# Shield_Amir_Shalev_V_0_0.net
KiCad netlist of a schematic drawn in EasyEDA
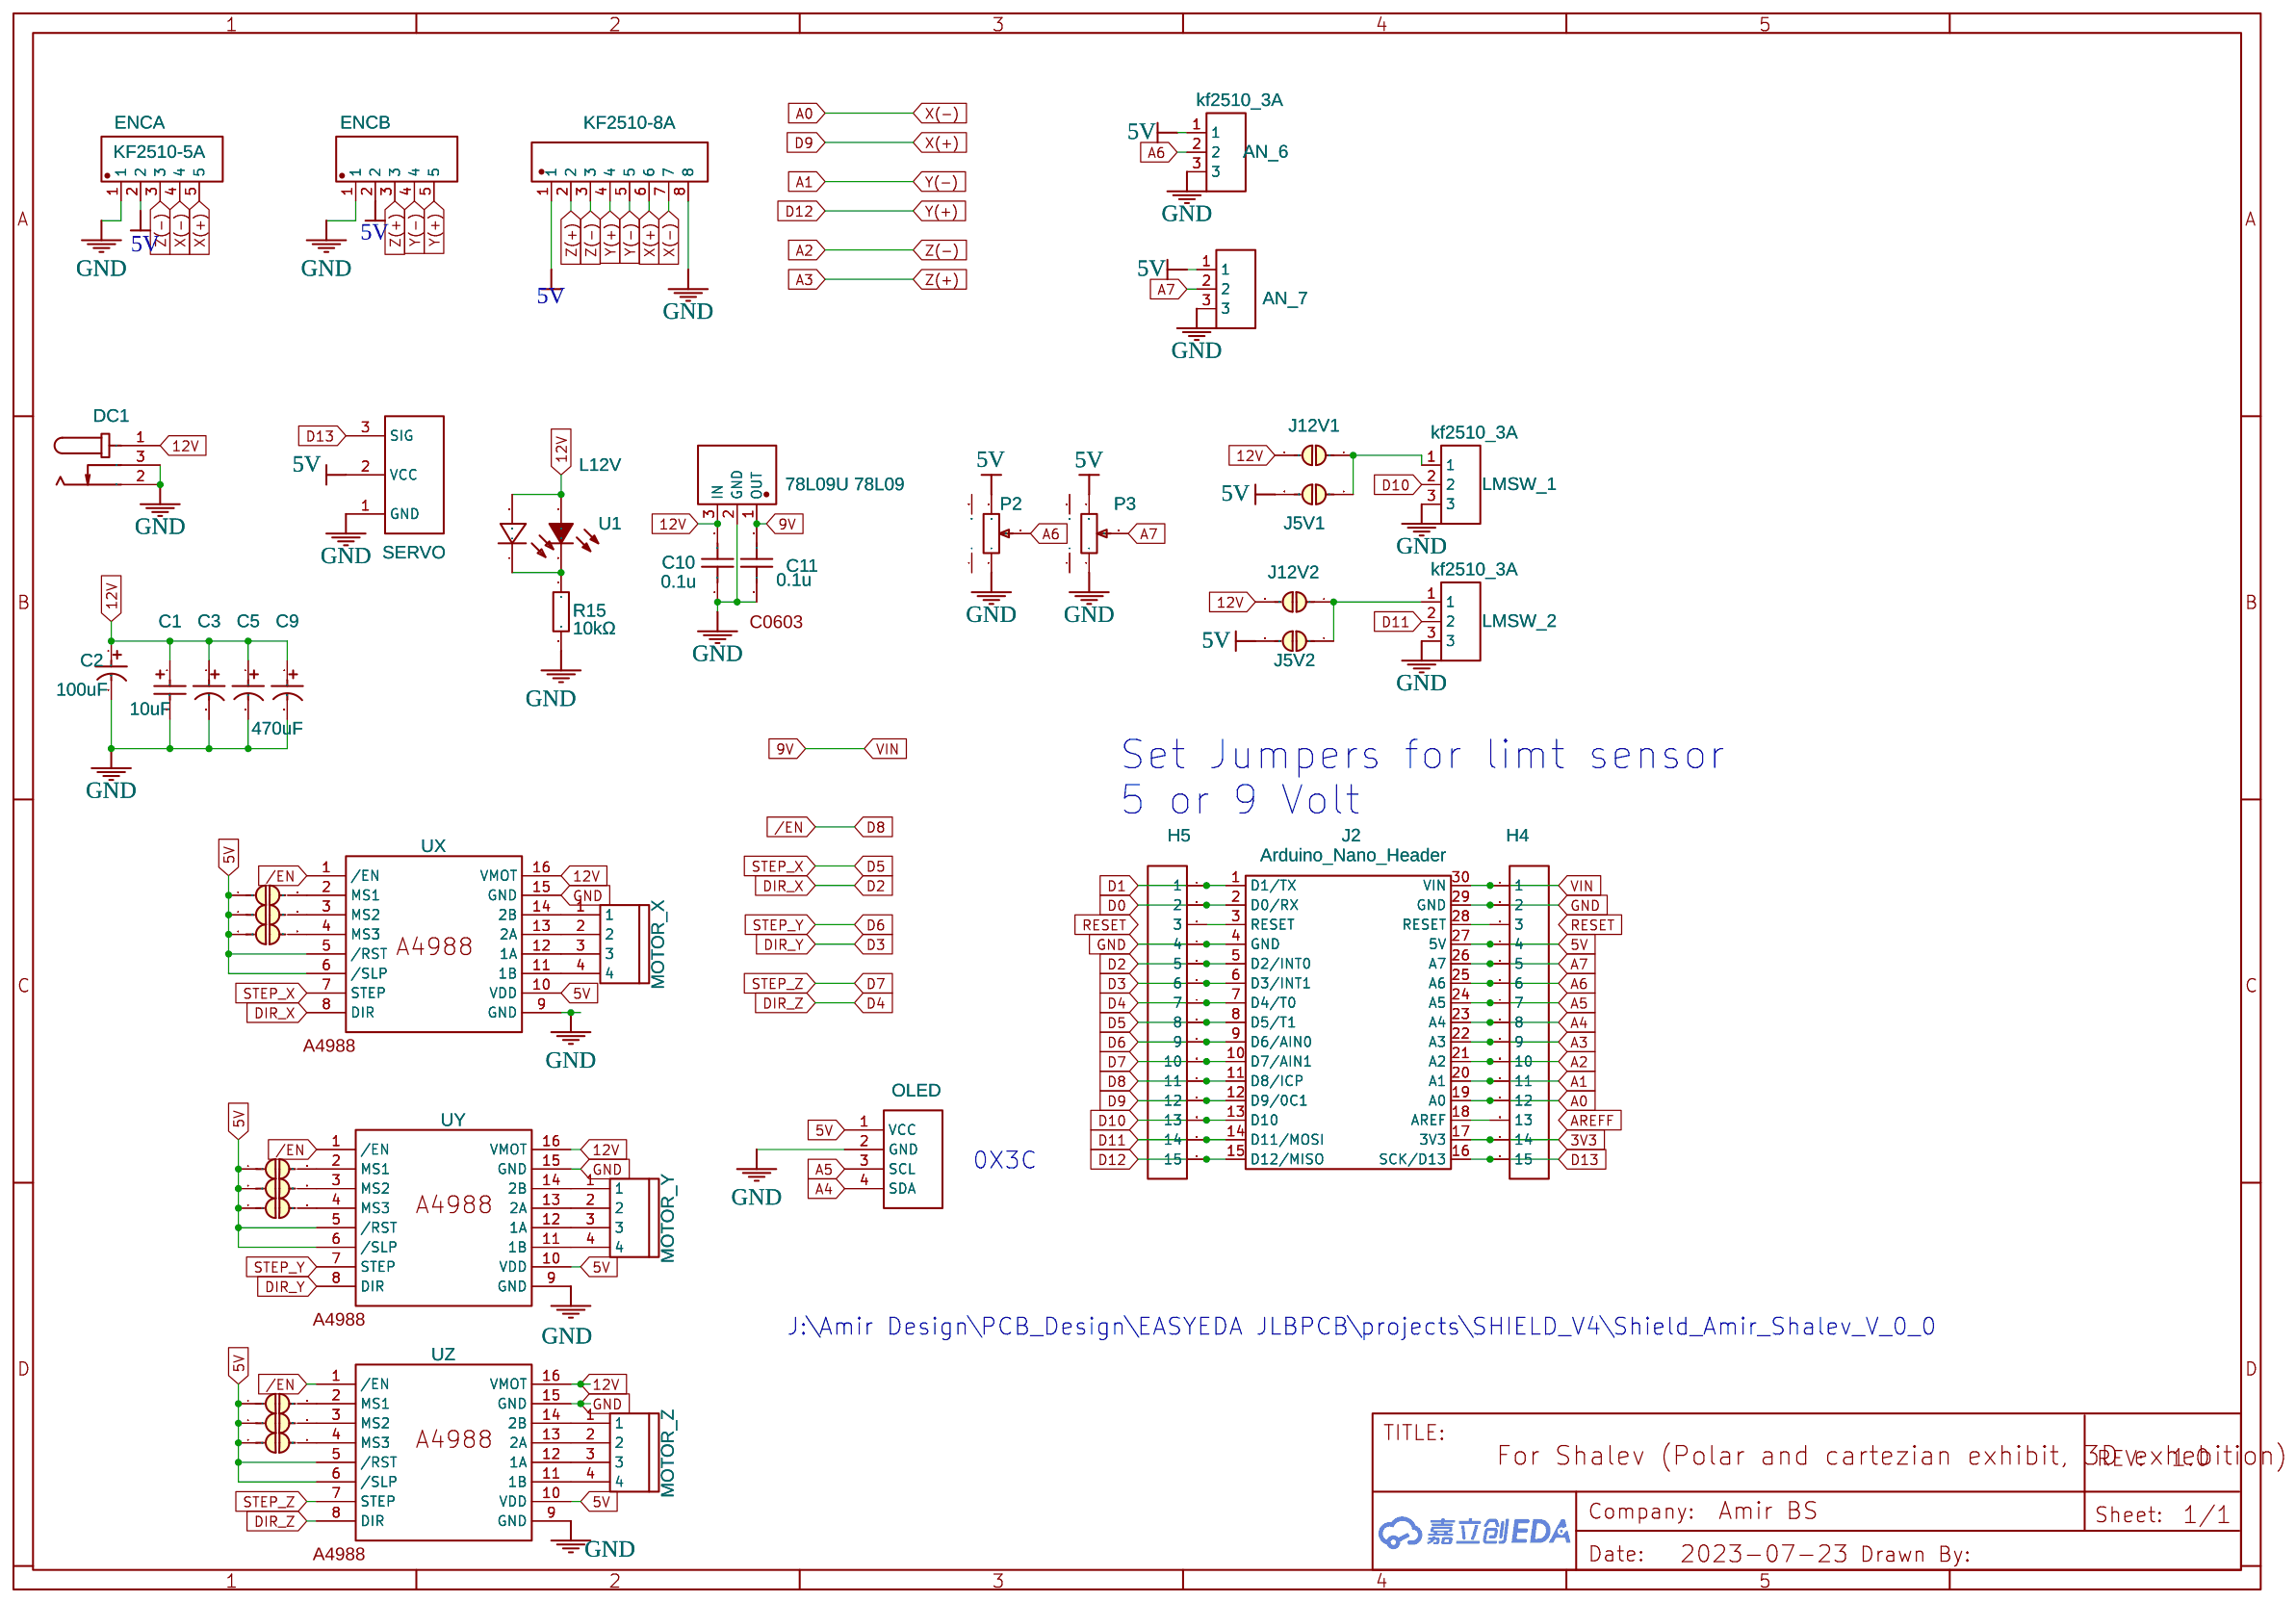
[diagram p0: schematic sheet]

(export (version "E")
  (design (tool "Eeschema 10.0.6"))
  (components
    (comp (ref "AN_6")
      (value "kf2510_3A")
      (fields (field (name "Manufacturer Part") "2510-3A") (field (name "Manufacturer") "BOOMELE(博穆精密)"))
      (libsource (lib "") (part "kf2510_3A_1"))
    )
    (comp (ref "AN_7")
      (value "kf2510_3A")
      (fields (field (name "Manufacturer Part") "2510-3A") (field (name "Manufacturer") "BOOMELE(博穆精密)"))
      (libsource (lib "") (part "kf2510_3A_1"))
    )
    (comp (ref "C1")
      (value "10uF")
      (fields (field (name "Manufacturer Part") "TAJA106K016RNJ") (field (name "Manufacturer") "Kyocera AVX"))
      (libsource (lib "") (part "TAJA106K016RNJ"))
    )
    (comp (ref "C2")
      (value "100uF")
      (fields
        (field (name "Manufacturer Part") "KM107M035E11RR0VH2FP0")
        (field (name "Manufacturer") "CX(承兴)")
      )
      (libsource (lib "") (part "100uF 35V 6.3*11"))
    )
    (comp (ref "C3")
      (value "470uF")
      (fields
        (field (name "Manufacturer Part") "GR477M025F12RR0VH4FP0")
        (field (name "Manufacturer") "CX(承兴)")
      )
      (libsource (lib "") (part "470uF 25V 8*12Black high frequency"))
    )
    (comp (ref "C5")
      (value "470uF")
      (fields
        (field (name "Manufacturer Part") "GR477M025F12RR0VH4FP0")
        (field (name "Manufacturer") "CX(承兴)")
      )
      (libsource (lib "") (part "470uF 25V 8*12Black high frequency"))
    )
    (comp (ref "C9")
      (value "470uF")
      (fields
        (field (name "Manufacturer Part") "GR477M025F12RR0VH4FP0")
        (field (name "Manufacturer") "CX(承兴)")
      )
      (libsource (lib "") (part "470uF 25V 8*12Black high frequency"))
    )
    (comp (ref "C10") (value "0.1u") (libsource (lib "") (part "C_0603_US")))
    (comp (ref "C11") (value "0.1u") (libsource (lib "") (part "C_0603_US_1")))
    (comp (ref "CN2")
      (value "KF2510-8A")
      (fields (field (name "Manufacturer Part") "2510-8A") (field (name "Manufacturer") "BOOMELE(博穆精密)"))
      (libsource (lib "") (part "KF2510-8A"))
    )
    (comp (ref "DC1")
      (value "DC")
      (fields
        (field (name "BOM_Manufacturer Part") "DC005-2.0MM")
        (field (name "BOM_Supplier Part") "C111567")
      )
      (libsource (lib "") (part "DC005-2.0MM"))
    )
    (comp (ref "ENCA")
      (value "KF2510-5A")
      (fields (field (name "Manufacturer Part") "2510-5A") (field (name "Manufacturer") "BOOMELE(博穆精密)"))
      (libsource (lib "") (part "KF2510-5A_1"))
    )
    (comp (ref "ENCB")
      (value "KF2510-5A")
      (fields (field (name "Manufacturer Part") "2510-5A") (field (name "Manufacturer") "BOOMELE(博穆精密)"))
      (libsource (lib "") (part "KF2510-5A"))
    )
    (comp (ref "H4")
      (value "HDR-F-2.54_1x15")
      (fields (field (name "BOM_Supplier Part") "C124408"))
      (libsource (lib "") (part "HDR-F-2.54_1x15"))
    )
    (comp (ref "H5")
      (value "HDR-F-2.54_1x15")
      (fields (field (name "BOM_Supplier Part") "C124408"))
      (libsource (lib "") (part "HDR-F-2.54_1x15_1"))
    )
    (comp (ref "J2") (value "Arduino_Nano_Header") (libsource (lib "") (part "Arduino_Nano_Header")))
    (comp (ref "J5V1") (value "JUMPER-SMT_2") (libsource (lib "") (part "JUMPER-SMT_2_3")))
    (comp (ref "J5V2") (value "JUMPER-SMT_2") (libsource (lib "") (part "JUMPER-SMT_2_3")))
    (comp (ref "J12V1") (value "JUMPER-SMT_2") (libsource (lib "") (part "JUMPER-SMT_2_4")))
    (comp (ref "J12V2") (value "JUMPER-SMT_2") (libsource (lib "") (part "JUMPER-SMT_2_4")))
    (comp (ref "JX1") (value "JUMPER-SMT_2") (libsource (lib "") (part "JUMPER-SMT_2")))
    (comp (ref "JX2") (value "JUMPER-SMT_2") (libsource (lib "") (part "JUMPER-SMT_2")))
    (comp (ref "JX3") (value "JUMPER-SMT_2") (libsource (lib "") (part "JUMPER-SMT_2")))
    (comp (ref "JY1") (value "JUMPER-SMT_2") (libsource (lib "") (part "JUMPER-SMT_2_1")))
    (comp (ref "JY2") (value "JUMPER-SMT_2") (libsource (lib "") (part "JUMPER-SMT_2_1")))
    (comp (ref "JY3") (value "JUMPER-SMT_2") (libsource (lib "") (part "JUMPER-SMT_2_1")))
    (comp (ref "JZ1") (value "JUMPER-SMT_2") (libsource (lib "") (part "JUMPER-SMT_2_2")))
    (comp (ref "JZ2") (value "JUMPER-SMT_2") (libsource (lib "") (part "JUMPER-SMT_2_2")))
    (comp (ref "JZ3") (value "JUMPER-SMT_2") (libsource (lib "") (part "JUMPER-SMT_2_2")))
    (comp (ref "L12V")
      (value "LED")
      (fields
        (field (name "BOM_Manufacturer Part") "19-217/BHC-ZL1M2RY/3T")
        (field (name "BOM_Supplier Part") "C72041")
      )
      (libsource (lib "") (part "19-217/BHC-ZL1M2RY/3T"))
    )
    (comp (ref "LMSW_1")
      (value "kf2510_3A")
      (fields (field (name "Manufacturer Part") "2510-3A") (field (name "Manufacturer") "BOOMELE(博穆精密)"))
      (libsource (lib "") (part "kf2510_3A"))
    )
    (comp (ref "LMSW_2")
      (value "kf2510_3A")
      (fields (field (name "Manufacturer Part") "2510-3A") (field (name "Manufacturer") "BOOMELE(博穆精密)"))
      (libsource (lib "") (part "kf2510_3A"))
    )
    (comp (ref "MOTOR_X")
      (value "XH2.54-4AW")
      (fields (field (name "Manufacturer Part") "XH-4AW") (field (name "Manufacturer") "BOOMELE(博穆精密)"))
      (libsource (lib "") (part "XH2.54-4AW"))
    )
    (comp (ref "MOTOR_Y")
      (value "XH2.54-4AW")
      (fields (field (name "Manufacturer Part") "XH-4AW") (field (name "Manufacturer") "BOOMELE(博穆精密)"))
      (libsource (lib "") (part "XH2.54-4AW_2"))
    )
    (comp (ref "MOTOR_Z")
      (value "XH2.54-4AW")
      (fields (field (name "Manufacturer Part") "XH-4AW") (field (name "Manufacturer") "BOOMELE(博穆精密)"))
      (libsource (lib "") (part "XH2.54-4AW_1"))
    )
    (comp (ref "OLED")
      (value "1.3 inch OLED SSH1106 I2C 128x64 copy")
      (libsource (lib "") (part "1.3 inch OLED SSH1106 I2C 128x64 copy"))
    )
    (comp (ref "P2")
      (value "长柄旋转电位器")
      (fields (field (name "BOM_Supplier Part") "C2874842"))
      (libsource (lib "") (part "长柄旋转电位器"))
    )
    (comp (ref "P3")
      (value "长柄旋转电位器")
      (fields (field (name "BOM_Supplier Part") "C2874842"))
      (libsource (lib "") (part "长柄旋转电位器"))
    )
    (comp (ref "R15")
      (value "10kΩ")
      (fields
        (field (name "BOM_Manufacturer Part") "0603WAF1002T5E")
        (field (name "BOM_Supplier Part") "C25804")
      )
      (libsource (lib "") (part "0603WAF1002T5E"))
    )
    (comp (ref "SERVO")
      (value "Servo+3d")
      (fields (field (name "BOM_Manufacturer Part") "New SchematicLib"))
      (libsource (lib "") (part "Servo+3d"))
    )
    (comp (ref "U1")
      (value "LED-DIP-3MM_RED")
      (fields (field (name "Manufacturer Part") "LED-DIP-3MM_Red"))
      (libsource (lib "") (part "LED-DIP-3MM_RED"))
    )
    (comp (ref "U5")
      (value "78L09U 78L09")
      (fields (field (name "Manufacturer") "CBI(创基)"))
      (libsource (lib "") (part "78L09U 78L09"))
    )
    (comp (ref "UX") (value "A4988") (libsource (lib "") (part "A4988_2")))
    (comp (ref "UY") (value "A4988") (libsource (lib "") (part "A4988")))
    (comp (ref "UZ") (value "A4988") (libsource (lib "") (part "A4988_1")))
  )
  (nets
    (net (code "1") (name "3V3") (class "Default")
      (node (ref "H4") (pin "14") (pinfunction "14_14") (pintype "unspecified"))
      (node (ref "J2") (pin "17") (pinfunction "3V3_17") (pintype "unspecified"))
    )
    (net (code "2") (name "5V") (class "Default")
      (node (ref "AN_6") (pin "1") (pinfunction "1_1") (pintype "unspecified"))
      (node (ref "AN_7") (pin "1") (pinfunction "1_1") (pintype "unspecified"))
      (node (ref "CN2") (pin "1") (pinfunction "1_1") (pintype "unspecified"))
      (node (ref "ENCA") (pin "2") (pinfunction "2_2") (pintype "unspecified"))
      (node (ref "ENCB") (pin "2") (pinfunction "2_2") (pintype "unspecified"))
      (node (ref "H4") (pin "4") (pinfunction "4_4") (pintype "unspecified"))
      (node (ref "J2") (pin "27") (pinfunction "5V_27") (pintype "unspecified"))
      (node (ref "J5V1") (pin "2") (pinfunction "2_2") (pintype "bidirectional"))
      (node (ref "J5V2") (pin "2") (pinfunction "2_2") (pintype "bidirectional"))
      (node (ref "JX1") (pin "1") (pinfunction "1_1") (pintype "bidirectional"))
      (node (ref "JX2") (pin "1") (pinfunction "1_1") (pintype "bidirectional"))
      (node (ref "JX3") (pin "1") (pinfunction "1_1") (pintype "bidirectional"))
      (node (ref "JY1") (pin "1") (pinfunction "1_1") (pintype "bidirectional"))
      (node (ref "JY2") (pin "1") (pinfunction "1_1") (pintype "bidirectional"))
      (node (ref "JY3") (pin "1") (pinfunction "1_1") (pintype "bidirectional"))
      (node (ref "JZ1") (pin "1") (pinfunction "1_1") (pintype "bidirectional"))
      (node (ref "JZ2") (pin "1") (pinfunction "1_1") (pintype "bidirectional"))
      (node (ref "JZ3") (pin "1") (pinfunction "1_1") (pintype "bidirectional"))
      (node (ref "OLED") (pin "1") (pinfunction "VCC_1") (pintype "passive"))
      (node (ref "P2") (pin "3") (pinfunction "3_3") (pintype "input"))
      (node (ref "P3") (pin "3") (pinfunction "3_3") (pintype "input"))
      (node (ref "SERVO") (pin "2") (pinfunction "VCC_2") (pintype "unspecified"))
      (node (ref "UX") (pin "10") (pinfunction "VDD_10") (pintype "unspecified"))
      (node (ref "UX") (pin "5") (pinfunction "/RST_5") (pintype "unspecified"))
      (node (ref "UX") (pin "6") (pinfunction "/SLP_6") (pintype "unspecified"))
      (node (ref "UY") (pin "10") (pinfunction "VDD_10") (pintype "unspecified"))
      (node (ref "UY") (pin "5") (pinfunction "/RST_5") (pintype "unspecified"))
      (node (ref "UY") (pin "6") (pinfunction "/SLP_6") (pintype "unspecified"))
      (node (ref "UZ") (pin "10") (pinfunction "VDD_10") (pintype "unspecified"))
      (node (ref "UZ") (pin "5") (pinfunction "/RST_5") (pintype "unspecified"))
      (node (ref "UZ") (pin "6") (pinfunction "/SLP_6") (pintype "unspecified"))
    )
    (net (code "3") (name "9V") (class "Default")
      (node (ref "C11") (pin "2") (pinfunction "2_2") (pintype "unspecified"))
      (node (ref "H4") (pin "1") (pinfunction "1_1") (pintype "unspecified"))
      (node (ref "J2") (pin "30") (pinfunction "VIN_30") (pintype "unspecified"))
      (node (ref "U5") (pin "1") (pinfunction "OUT_1") (pintype "unspecified"))
    )
    (net (code "4") (name "12V") (class "Default")
      (node (ref "C1") (pin "1") (pinfunction "1_1") (pintype "input"))
      (node (ref "C10") (pin "2") (pinfunction "2_2") (pintype "unspecified"))
      (node (ref "C2") (pin "1") (pinfunction "1_1") (pintype "input"))
      (node (ref "C3") (pin "1") (pinfunction "1_1") (pintype "input"))
      (node (ref "C5") (pin "1") (pinfunction "1_1") (pintype "input"))
      (node (ref "C9") (pin "1") (pinfunction "1_1") (pintype "input"))
      (node (ref "DC1") (pin "1") (pinfunction "1_1") (pintype "unspecified"))
      (node (ref "J12V1") (pin "2") (pinfunction "2_2") (pintype "bidirectional"))
      (node (ref "J12V2") (pin "2") (pinfunction "2_2") (pintype "bidirectional"))
      (node (ref "L12V") (pin "1") (pinfunction "A_1") (pintype "input"))
      (node (ref "U1") (pin "2") (pinfunction "2_2") (pintype "unspecified"))
      (node (ref "U5") (pin "3") (pinfunction "IN_3") (pintype "unspecified"))
      (node (ref "UX") (pin "16") (pinfunction "VMOT_16") (pintype "unspecified"))
      (node (ref "UY") (pin "16") (pinfunction "VMOT_16") (pintype "unspecified"))
      (node (ref "UZ") (pin "16") (pinfunction "VMOT_16") (pintype "unspecified"))
    )
    (net (code "5") (name "A0") (class "Default")
      (node (ref "CN2") (pin "7") (pinfunction "7_7") (pintype "unspecified"))
      (node (ref "ENCA") (pin "4") (pinfunction "4_4") (pintype "unspecified"))
      (node (ref "H4") (pin "12") (pinfunction "12_12") (pintype "unspecified"))
      (node (ref "J2") (pin "19") (pinfunction "A0_19") (pintype "unspecified"))
    )
    (net (code "6") (name "A1") (class "Default")
      (node (ref "CN2") (pin "5") (pinfunction "5_5") (pintype "unspecified"))
      (node (ref "ENCB") (pin "4") (pinfunction "4_4") (pintype "unspecified"))
      (node (ref "H4") (pin "11") (pinfunction "11_11") (pintype "unspecified"))
      (node (ref "J2") (pin "20") (pinfunction "A1_20") (pintype "unspecified"))
    )
    (net (code "7") (name "A2") (class "Default")
      (node (ref "CN2") (pin "3") (pinfunction "3_3") (pintype "unspecified"))
      (node (ref "ENCA") (pin "3") (pinfunction "3_3") (pintype "unspecified"))
      (node (ref "H4") (pin "10") (pinfunction "10_10") (pintype "unspecified"))
      (node (ref "J2") (pin "21") (pinfunction "A2_21") (pintype "unspecified"))
    )
    (net (code "8") (name "A3") (class "Default")
      (node (ref "CN2") (pin "2") (pinfunction "2_2") (pintype "unspecified"))
      (node (ref "ENCB") (pin "3") (pinfunction "3_3") (pintype "unspecified"))
      (node (ref "H4") (pin "9") (pinfunction "9_9") (pintype "unspecified"))
      (node (ref "J2") (pin "22") (pinfunction "A3_22") (pintype "unspecified"))
    )
    (net (code "9") (name "A4") (class "Default")
      (node (ref "H4") (pin "8") (pinfunction "8_8") (pintype "unspecified"))
      (node (ref "J2") (pin "23") (pinfunction "A4_23") (pintype "unspecified"))
      (node (ref "OLED") (pin "4") (pinfunction "SDA_4") (pintype "bidirectional"))
    )
    (net (code "10") (name "A5") (class "Default")
      (node (ref "H4") (pin "7") (pinfunction "7_7") (pintype "unspecified"))
      (node (ref "J2") (pin "24") (pinfunction "A5_24") (pintype "unspecified"))
      (node (ref "OLED") (pin "3") (pinfunction "SCL_3") (pintype "bidirectional"))
    )
    (net (code "11") (name "A6") (class "Default")
      (node (ref "AN_6") (pin "2") (pinfunction "2_2") (pintype "unspecified"))
      (node (ref "H4") (pin "6") (pinfunction "6_6") (pintype "unspecified"))
      (node (ref "J2") (pin "25") (pinfunction "A6_25") (pintype "unspecified"))
      (node (ref "P2") (pin "2") (pinfunction "2_2") (pintype "input"))
    )
    (net (code "12") (name "A7") (class "Default")
      (node (ref "AN_7") (pin "2") (pinfunction "2_2") (pintype "unspecified"))
      (node (ref "H4") (pin "5") (pinfunction "5_5") (pintype "unspecified"))
      (node (ref "J2") (pin "26") (pinfunction "A7_26") (pintype "unspecified"))
      (node (ref "P3") (pin "2") (pinfunction "2_2") (pintype "input"))
    )
    (net (code "14") (name "D0") (class "Default")
      (node (ref "H5") (pin "2") (pinfunction "2_2") (pintype "unspecified"))
      (node (ref "J2") (pin "2") (pinfunction "D0/RX_2") (pintype "unspecified"))
    )
    (net (code "15") (name "D1") (class "Default")
      (node (ref "H5") (pin "1") (pinfunction "1_1") (pintype "unspecified"))
      (node (ref "J2") (pin "1") (pinfunction "D1/TX_1") (pintype "unspecified"))
    )
    (net (code "16") (name "D2") (class "Default")
      (node (ref "H5") (pin "5") (pinfunction "5_5") (pintype "unspecified"))
      (node (ref "J2") (pin "5") (pinfunction "D2/INT0_5") (pintype "unspecified"))
      (node (ref "UX") (pin "8") (pinfunction "DIR_8") (pintype "unspecified"))
    )
    (net (code "17") (name "D3") (class "Default")
      (node (ref "H5") (pin "6") (pinfunction "6_6") (pintype "unspecified"))
      (node (ref "J2") (pin "6") (pinfunction "D3/INT1_6") (pintype "unspecified"))
      (node (ref "UY") (pin "8") (pinfunction "DIR_8") (pintype "unspecified"))
    )
    (net (code "18") (name "D4") (class "Default")
      (node (ref "H5") (pin "7") (pinfunction "7_7") (pintype "unspecified"))
      (node (ref "J2") (pin "7") (pinfunction "D4/T0_7") (pintype "unspecified"))
      (node (ref "UZ") (pin "8") (pinfunction "DIR_8") (pintype "unspecified"))
    )
    (net (code "19") (name "D5") (class "Default")
      (node (ref "H5") (pin "8") (pinfunction "8_8") (pintype "unspecified"))
      (node (ref "J2") (pin "8") (pinfunction "D5/T1_8") (pintype "unspecified"))
      (node (ref "UX") (pin "7") (pinfunction "STEP_7") (pintype "unspecified"))
    )
    (net (code "20") (name "D6") (class "Default")
      (node (ref "H5") (pin "9") (pinfunction "9_9") (pintype "unspecified"))
      (node (ref "J2") (pin "9") (pinfunction "D6/AIN0_9") (pintype "unspecified"))
      (node (ref "UY") (pin "7") (pinfunction "STEP_7") (pintype "unspecified"))
    )
    (net (code "21") (name "D7") (class "Default")
      (node (ref "H5") (pin "10") (pinfunction "10_10") (pintype "unspecified"))
      (node (ref "J2") (pin "10") (pinfunction "D7/AIN1_10") (pintype "unspecified"))
      (node (ref "UZ") (pin "7") (pinfunction "STEP_7") (pintype "unspecified"))
    )
    (net (code "22") (name "D8") (class "Default")
      (node (ref "H5") (pin "11") (pinfunction "11_11") (pintype "unspecified"))
      (node (ref "J2") (pin "11") (pinfunction "D8/ICP_11") (pintype "unspecified"))
      (node (ref "UX") (pin "1") (pinfunction "/EN_1") (pintype "unspecified"))
      (node (ref "UY") (pin "1") (pinfunction "/EN_1") (pintype "unspecified"))
      (node (ref "UZ") (pin "1") (pinfunction "/EN_1") (pintype "unspecified"))
    )
    (net (code "23") (name "D9") (class "Default")
      (node (ref "CN2") (pin "6") (pinfunction "6_6") (pintype "unspecified"))
      (node (ref "ENCA") (pin "5") (pinfunction "5_5") (pintype "unspecified"))
      (node (ref "H5") (pin "12") (pinfunction "12_12") (pintype "unspecified"))
      (node (ref "J2") (pin "12") (pinfunction "D9/0C1_12") (pintype "unspecified"))
    )
    (net (code "24") (name "D10") (class "Default")
      (node (ref "H5") (pin "13") (pinfunction "13_13") (pintype "unspecified"))
      (node (ref "J2") (pin "13") (pinfunction "D10_13") (pintype "unspecified"))
      (node (ref "LMSW_1") (pin "2") (pinfunction "2_2") (pintype "unspecified"))
    )
    (net (code "25") (name "D11") (class "Default")
      (node (ref "H5") (pin "14") (pinfunction "14_14") (pintype "unspecified"))
      (node (ref "J2") (pin "14") (pinfunction "D11/MOSI_14") (pintype "unspecified"))
      (node (ref "LMSW_2") (pin "2") (pinfunction "2_2") (pintype "unspecified"))
    )
    (net (code "26") (name "D12") (class "Default")
      (node (ref "CN2") (pin "4") (pinfunction "4_4") (pintype "unspecified"))
      (node (ref "ENCB") (pin "5") (pinfunction "5_5") (pintype "unspecified"))
      (node (ref "H5") (pin "15") (pinfunction "15_15") (pintype "unspecified"))
      (node (ref "J2") (pin "15") (pinfunction "D12/MISO_15") (pintype "unspecified"))
    )
    (net (code "27") (name "D13") (class "Default")
      (node (ref "H4") (pin "15") (pinfunction "15_15") (pintype "unspecified"))
      (node (ref "J2") (pin "16") (pinfunction "SCK/D13_16") (pintype "unspecified"))
      (node (ref "SERVO") (pin "3") (pinfunction "SIG_3") (pintype "unspecified"))
    )
    (net (code "28") (name "GND") (class "Default")
      (node (ref "AN_6") (pin "3") (pinfunction "3_3") (pintype "unspecified"))
      (node (ref "AN_7") (pin "3") (pinfunction "3_3") (pintype "unspecified"))
      (node (ref "C1") (pin "2") (pinfunction "2_2") (pintype "input"))
      (node (ref "C10") (pin "1") (pinfunction "1_1") (pintype "unspecified"))
      (node (ref "C11") (pin "1") (pinfunction "1_1") (pintype "unspecified"))
      (node (ref "C2") (pin "2") (pinfunction "2_2") (pintype "input"))
      (node (ref "C3") (pin "2") (pinfunction "2_2") (pintype "input"))
      (node (ref "C5") (pin "2") (pinfunction "2_2") (pintype "input"))
      (node (ref "C9") (pin "2") (pinfunction "2_2") (pintype "input"))
      (node (ref "CN2") (pin "8") (pinfunction "8_8") (pintype "unspecified"))
      (node (ref "DC1") (pin "2") (pinfunction "2_2") (pintype "unspecified"))
      (node (ref "DC1") (pin "3") (pinfunction "3_3") (pintype "unspecified"))
      (node (ref "ENCA") (pin "1") (pinfunction "1_1") (pintype "unspecified"))
      (node (ref "ENCB") (pin "1") (pinfunction "1_1") (pintype "unspecified"))
      (node (ref "H4") (pin "2") (pinfunction "2_2") (pintype "unspecified"))
      (node (ref "H5") (pin "4") (pinfunction "4_4") (pintype "unspecified"))
      (node (ref "J2") (pin "29") (pinfunction "GND_29") (pintype "unspecified"))
      (node (ref "J2") (pin "4") (pinfunction "GND_4") (pintype "unspecified"))
      (node (ref "LMSW_1") (pin "3") (pinfunction "3_3") (pintype "unspecified"))
      (node (ref "LMSW_2") (pin "3") (pinfunction "3_3") (pintype "unspecified"))
      (node (ref "OLED") (pin "2") (pinfunction "GND_2") (pintype "passive"))
      (node (ref "P2") (pin "1") (pinfunction "1_1") (pintype "input"))
      (node (ref "P3") (pin "1") (pinfunction "1_1") (pintype "input"))
      (node (ref "R15") (pin "2") (pinfunction "2_2") (pintype "input"))
      (node (ref "SERVO") (pin "1") (pinfunction "GND_1") (pintype "unspecified"))
      (node (ref "U5") (pin "2") (pinfunction "GND_2") (pintype "unspecified"))
      (node (ref "UX") (pin "15") (pinfunction "GND_15") (pintype "unspecified"))
      (node (ref "UX") (pin "9") (pinfunction "GND_9") (pintype "unspecified"))
      (node (ref "UY") (pin "15") (pinfunction "GND_15") (pintype "unspecified"))
      (node (ref "UY") (pin "9") (pinfunction "GND_9") (pintype "unspecified"))
      (node (ref "UZ") (pin "15") (pinfunction "GND_15") (pintype "unspecified"))
      (node (ref "UZ") (pin "9") (pinfunction "GND_9") (pintype "unspecified"))
    )
    (net (code "29") (name "Net-(H4-Pad3)") (class "Default")
      (node (ref "H4") (pin "3") (pinfunction "3_3") (pintype "unspecified"))
      (node (ref "J2") (pin "28") (pinfunction "RESET_28") (pintype "unspecified"))
    )
    (net (code "30") (name "Net-(H5-Pad3)") (class "Default")
      (node (ref "H5") (pin "3") (pinfunction "3_3") (pintype "unspecified"))
      (node (ref "J2") (pin "3") (pinfunction "RESET_3") (pintype "unspecified"))
    )
    (net (code "31") (name "Net-(J2-AREF)") (class "Default")
      (node (ref "H4") (pin "13") (pinfunction "13_13") (pintype "unspecified"))
      (node (ref "J2") (pin "18") (pinfunction "AREF_18") (pintype "unspecified"))
    )
    (net (code "32") (name "Net-(J12V1-Pad1)") (class "Default")
      (node (ref "J12V1") (pin "1") (pinfunction "1_1") (pintype "bidirectional"))
      (node (ref "J5V1") (pin "1") (pinfunction "1_1") (pintype "bidirectional"))
      (node (ref "LMSW_1") (pin "1") (pinfunction "1_1") (pintype "unspecified"))
    )
    (net (code "33") (name "Net-(J12V2-Pad1)") (class "Default")
      (node (ref "J12V2") (pin "1") (pinfunction "1_1") (pintype "bidirectional"))
      (node (ref "J5V2") (pin "1") (pinfunction "1_1") (pintype "bidirectional"))
      (node (ref "LMSW_2") (pin "1") (pinfunction "1_1") (pintype "unspecified"))
    )
    (net (code "34") (name "Net-(L12V-C)") (class "Default")
      (node (ref "L12V") (pin "2") (pinfunction "C_2") (pintype "input"))
      (node (ref "R15") (pin "1") (pinfunction "1_1") (pintype "input"))
      (node (ref "U1") (pin "1") (pinfunction "1_1") (pintype "unspecified"))
    )
    (net (code "35") (name "Net-(UX-1A)") (class "Default")
      (node (ref "MOTOR_X") (pin "3") (pinfunction "3_3") (pintype "unspecified"))
      (node (ref "UX") (pin "12") (pinfunction "1A_12") (pintype "unspecified"))
    )
    (net (code "36") (name "Net-(UX-1B)") (class "Default")
      (node (ref "MOTOR_X") (pin "4") (pinfunction "4_4") (pintype "unspecified"))
      (node (ref "UX") (pin "11") (pinfunction "1B_11") (pintype "unspecified"))
    )
    (net (code "37") (name "Net-(UX-2A)") (class "Default")
      (node (ref "MOTOR_X") (pin "2") (pinfunction "2_2") (pintype "unspecified"))
      (node (ref "UX") (pin "13") (pinfunction "2A_13") (pintype "unspecified"))
    )
    (net (code "38") (name "Net-(UX-2B)") (class "Default")
      (node (ref "MOTOR_X") (pin "1") (pinfunction "1_1") (pintype "unspecified"))
      (node (ref "UX") (pin "14") (pinfunction "2B_14") (pintype "unspecified"))
    )
    (net (code "39") (name "Net-(UX-MS1)") (class "Default")
      (node (ref "JX1") (pin "2") (pinfunction "2_2") (pintype "bidirectional"))
      (node (ref "UX") (pin "2") (pinfunction "MS1_2") (pintype "unspecified"))
    )
    (net (code "40") (name "Net-(UX-MS2)") (class "Default")
      (node (ref "JX2") (pin "2") (pinfunction "2_2") (pintype "bidirectional"))
      (node (ref "UX") (pin "3") (pinfunction "MS2_3") (pintype "unspecified"))
    )
    (net (code "41") (name "Net-(UX-MS3)") (class "Default")
      (node (ref "JX3") (pin "2") (pinfunction "2_2") (pintype "bidirectional"))
      (node (ref "UX") (pin "4") (pinfunction "MS3_4") (pintype "unspecified"))
    )
    (net (code "42") (name "Net-(UY-1A)") (class "Default")
      (node (ref "MOTOR_Y") (pin "3") (pinfunction "3_3") (pintype "unspecified"))
      (node (ref "UY") (pin "12") (pinfunction "1A_12") (pintype "unspecified"))
    )
    (net (code "43") (name "Net-(UY-1B)") (class "Default")
      (node (ref "MOTOR_Y") (pin "4") (pinfunction "4_4") (pintype "unspecified"))
      (node (ref "UY") (pin "11") (pinfunction "1B_11") (pintype "unspecified"))
    )
    (net (code "44") (name "Net-(UY-2A)") (class "Default")
      (node (ref "MOTOR_Y") (pin "2") (pinfunction "2_2") (pintype "unspecified"))
      (node (ref "UY") (pin "13") (pinfunction "2A_13") (pintype "unspecified"))
    )
    (net (code "45") (name "Net-(UY-2B)") (class "Default")
      (node (ref "MOTOR_Y") (pin "1") (pinfunction "1_1") (pintype "unspecified"))
      (node (ref "UY") (pin "14") (pinfunction "2B_14") (pintype "unspecified"))
    )
    (net (code "46") (name "Net-(UY-MS1)") (class "Default")
      (node (ref "JY1") (pin "2") (pinfunction "2_2") (pintype "bidirectional"))
      (node (ref "UY") (pin "2") (pinfunction "MS1_2") (pintype "unspecified"))
    )
    (net (code "47") (name "Net-(UY-MS2)") (class "Default")
      (node (ref "JY2") (pin "2") (pinfunction "2_2") (pintype "bidirectional"))
      (node (ref "UY") (pin "3") (pinfunction "MS2_3") (pintype "unspecified"))
    )
    (net (code "48") (name "Net-(UY-MS3)") (class "Default")
      (node (ref "JY3") (pin "2") (pinfunction "2_2") (pintype "bidirectional"))
      (node (ref "UY") (pin "4") (pinfunction "MS3_4") (pintype "unspecified"))
    )
    (net (code "49") (name "Net-(UZ-1A)") (class "Default")
      (node (ref "MOTOR_Z") (pin "3") (pinfunction "3_3") (pintype "unspecified"))
      (node (ref "UZ") (pin "12") (pinfunction "1A_12") (pintype "unspecified"))
    )
    (net (code "50") (name "Net-(UZ-1B)") (class "Default")
      (node (ref "MOTOR_Z") (pin "4") (pinfunction "4_4") (pintype "unspecified"))
      (node (ref "UZ") (pin "11") (pinfunction "1B_11") (pintype "unspecified"))
    )
    (net (code "51") (name "Net-(UZ-2A)") (class "Default")
      (node (ref "MOTOR_Z") (pin "2") (pinfunction "2_2") (pintype "unspecified"))
      (node (ref "UZ") (pin "13") (pinfunction "2A_13") (pintype "unspecified"))
    )
    (net (code "52") (name "Net-(UZ-2B)") (class "Default")
      (node (ref "MOTOR_Z") (pin "1") (pinfunction "1_1") (pintype "unspecified"))
      (node (ref "UZ") (pin "14") (pinfunction "2B_14") (pintype "unspecified"))
    )
    (net (code "53") (name "Net-(UZ-MS1)") (class "Default")
      (node (ref "JZ1") (pin "2") (pinfunction "2_2") (pintype "bidirectional"))
      (node (ref "UZ") (pin "2") (pinfunction "MS1_2") (pintype "unspecified"))
    )
    (net (code "54") (name "Net-(UZ-MS2)") (class "Default")
      (node (ref "JZ2") (pin "2") (pinfunction "2_2") (pintype "bidirectional"))
      (node (ref "UZ") (pin "3") (pinfunction "MS2_3") (pintype "unspecified"))
    )
    (net (code "55") (name "Net-(UZ-MS3)") (class "Default")
      (node (ref "JZ3") (pin "2") (pinfunction "2_2") (pintype "bidirectional"))
      (node (ref "UZ") (pin "4") (pinfunction "MS3_4") (pintype "unspecified"))
    )
    (net (code "57") (name "unconnected-(P2-Pad4)") (class "Default")
      (node (ref "P2") (pin "4") (pinfunction "4_4") (pintype "input"))
    )
    (net (code "58") (name "unconnected-(P2-Pad5)") (class "Default")
      (node (ref "P2") (pin "5") (pinfunction "5_5") (pintype "input"))
    )
    (net (code "59") (name "unconnected-(P3-Pad4)") (class "Default")
      (node (ref "P3") (pin "4") (pinfunction "4_4") (pintype "input"))
    )
    (net (code "60") (name "unconnected-(P3-Pad5)") (class "Default")
      (node (ref "P3") (pin "5") (pinfunction "5_5") (pintype "input"))
    )
  )
)
